# Set_Timer.net
KiCad netlist of a schematic drawn in Altium Designer
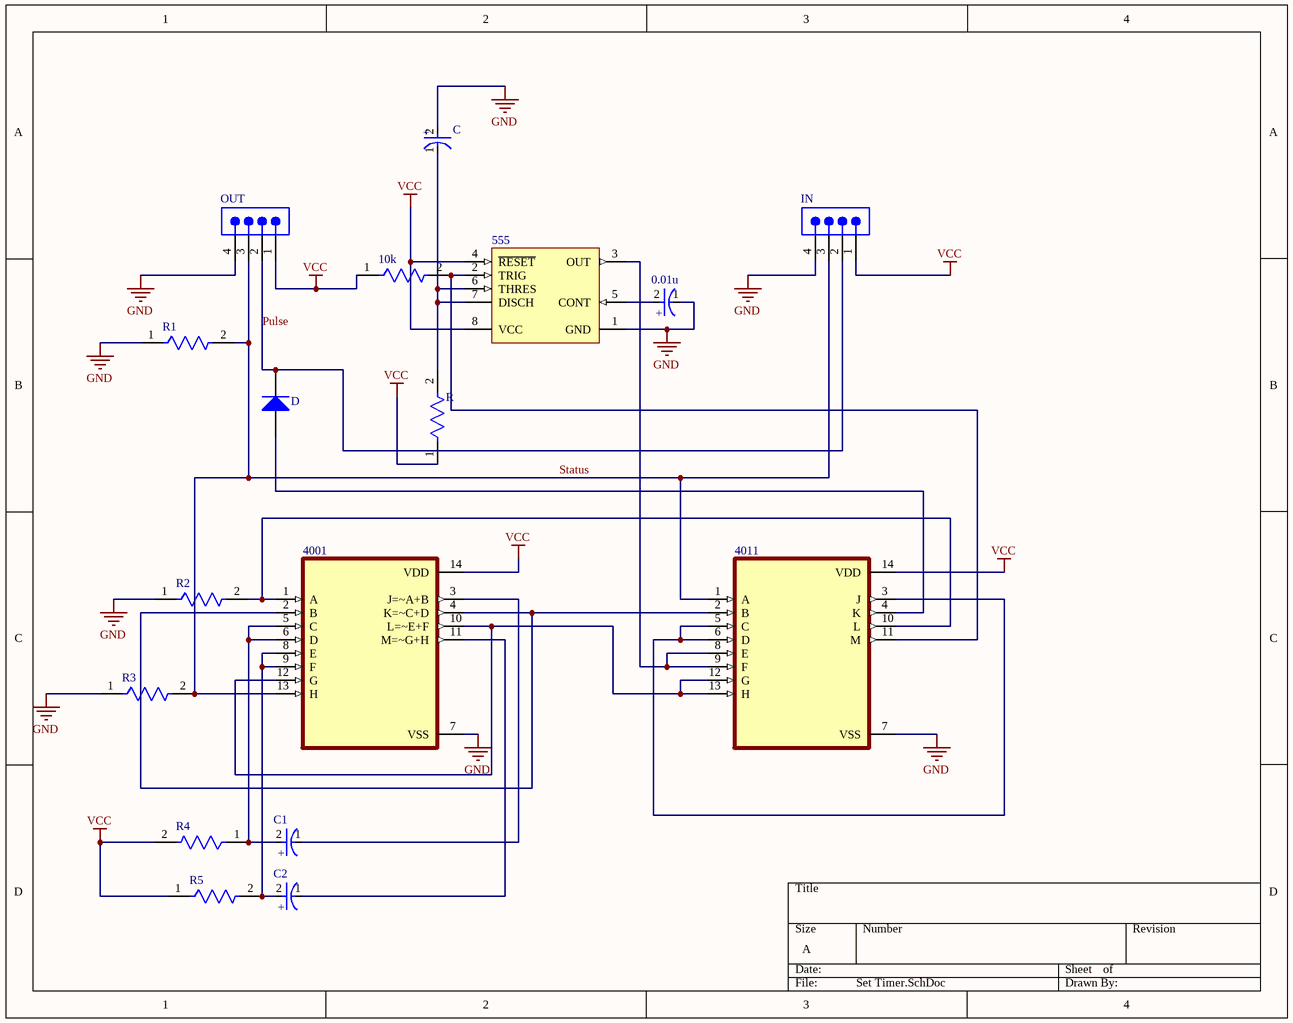
[diagram p0: Set Timer.SchDoc]

(export (version "E")
  (design (tool "Eeschema 10.0.6"))
  (components
    (comp (ref "0.01u")
      (value "EEUHD1H330")
      (footprint "FP-RAD-TH-D_5_0_5-L_11_1-MFG")
      (description "Aluminum Electrolytic Capacitors (Radial Lead Type) AEC-Q200 Qualified 33uF ±20% 50V")
      (fields (field (name "TOLERANCE") "20%") (field (name "VOLTAGE") "50V"))
      (libsource (lib "Altium Content Vault") (part "a00bbbee19879c290e62620ae7e47b1"))
    )
    (comp (ref "10k")
      (value "RR01J100KTB")
      (footprint "FP-RR01-MFG")
      (description "RES 100K OHM 5% 1W AXIAL")
      (fields (field (name "TOLERANCE") "5%"))
      (libsource (lib "Altium Content Vault") (part "1029c3af85768c4190bb7ad29bc67b5"))
    )
    (comp (ref "555")
      (value "NE555P")
      (footprint "P0008A")
      (description "Precision Timer, 4.5 to 16 V, 0 to 70 degC, 8-Pin DIP, Pb-Free, Tube")
      (fields (field (name "MANUFACTURER") "TexasInstruments"))
      (libsource (lib "Altium Content Vault") (part "TI-NE555-P8"))
    )
    (comp (ref "4001")
      (value "CD4001BE")
      (footprint "DIP794W45P254L1969H508Q14")
      (description "CMOS Quad 2-Input NOR Gate 14-PDIP -55 to 125")
      (fields (field (name "MF") "Texas Instruments"))
      (libsource (lib "CD4001BE") (part "CD4001BE"))
    )
    (comp (ref "4011")
      (value "CD4011BE")
      (footprint "DIP794W45P254L1969H508Q14")
      (libsource (lib "CD4011BE") (part "CD4011BE"))
    )
    (comp (ref "C")
      (value "EEUHD1H330")
      (footprint "FP-RAD-TH-D_5_0_5-L_11_1-MFG")
      (description "Aluminum Electrolytic Capacitors (Radial Lead Type) AEC-Q200 Qualified 33uF ±20% 50V")
      (fields (field (name "TOLERANCE") "20%") (field (name "VOLTAGE") "50V"))
      (libsource (lib "Altium Content Vault") (part "a00bbbee19879c290e62620ae7e47b1"))
    )
    (comp (ref "C1")
      (value "EEUHD1H330")
      (footprint "FP-RAD-TH-D_5_0_5-L_11_1-MFG")
      (description "Aluminum Electrolytic Capacitors (Radial Lead Type) AEC-Q200 Qualified 33uF ±20% 50V")
      (fields (field (name "TOLERANCE") "20%") (field (name "VOLTAGE") "50V"))
      (libsource (lib "Altium Content Vault") (part "a00bbbee19879c290e62620ae7e47b1"))
    )
    (comp (ref "C2")
      (value "EEUHD1H330")
      (footprint "FP-RAD-TH-D_5_0_5-L_11_1-MFG")
      (description "Aluminum Electrolytic Capacitors (Radial Lead Type) AEC-Q200 Qualified 33uF ±20% 50V")
      (fields (field (name "TOLERANCE") "20%") (field (name "VOLTAGE") "50V"))
      (libsource (lib "Altium Content Vault") (part "a00bbbee19879c290e62620ae7e47b1"))
    )
    (comp (ref "D")
      (value "1N4001-T")
      (footprint "DIOD-DO-41-P-2_V")
      (description "1.0 A Rectifier, 15 pF, 50 V, -65 to 150 degC, 2-Pin DO-41 Plastic, RoHS, Tape and Reel")
      (fields (field (name "MANUFACTURER") "Diodes Inc"))
      (libsource (lib "Altium Content Vault") (part "DIOD-D-A1K2-2"))
    )
    (comp (ref "IN")
      (value "TSW-104-08-L-S")
      (footprint "SMTC-TSW-104-08-X-S")
      (description "0.025\" SQ Post Header, Through-hole, Vertical, -55 to 125 degC, 2.54 mm Pitch, 4-Pin, Male, RoHS")
      (fields (field (name "MANUFACTURER") "Samtec"))
      (libsource (lib "Altium Content Vault") (part "SMTC-TSW-104-08-X-S"))
    )
    (comp (ref "OUT")
      (value "TSW-104-08-L-S")
      (footprint "SMTC-TSW-104-08-X-S")
      (description "0.025\" SQ Post Header, Through-hole, Vertical, -55 to 125 degC, 2.54 mm Pitch, 4-Pin, Male, RoHS")
      (fields (field (name "MANUFACTURER") "Samtec"))
      (libsource (lib "Altium Content Vault") (part "SMTC-TSW-104-08-X-S"))
    )
    (comp (ref "R")
      (value "RR01J100KTB")
      (footprint "FP-RR01-MFG")
      (description "RES 100K OHM 5% 1W AXIAL")
      (fields (field (name "TOLERANCE") "5%"))
      (libsource (lib "Altium Content Vault") (part "1029c3af85768c4190bb7ad29bc67b5"))
    )
    (comp (ref "R1")
      (value "RR01J100KTB")
      (footprint "FP-RR01-MFG")
      (description "RES 100K OHM 5% 1W AXIAL")
      (fields (field (name "TOLERANCE") "5%"))
      (libsource (lib "Altium Content Vault") (part "1029c3af85768c4190bb7ad29bc67b5"))
    )
    (comp (ref "R2")
      (value "RR01J100KTB")
      (footprint "FP-RR01-MFG")
      (description "RES 100K OHM 5% 1W AXIAL")
      (fields (field (name "TOLERANCE") "5%"))
      (libsource (lib "Altium Content Vault") (part "1029c3af85768c4190bb7ad29bc67b5"))
    )
    (comp (ref "R3")
      (value "RR01J100KTB")
      (footprint "FP-RR01-MFG")
      (description "RES 100K OHM 5% 1W AXIAL")
      (fields (field (name "TOLERANCE") "5%"))
      (libsource (lib "Altium Content Vault") (part "1029c3af85768c4190bb7ad29bc67b5"))
    )
    (comp (ref "R4")
      (value "RR01J100KTB")
      (footprint "FP-RR01-MFG")
      (description "RES 100K OHM 5% 1W AXIAL")
      (fields (field (name "TOLERANCE") "5%"))
      (libsource (lib "Altium Content Vault") (part "1029c3af85768c4190bb7ad29bc67b5"))
    )
    (comp (ref "R5")
      (value "RR01J100KTB")
      (footprint "FP-RR01-MFG")
      (description "RES 100K OHM 5% 1W AXIAL")
      (fields (field (name "TOLERANCE") "5%"))
      (libsource (lib "Altium Content Vault") (part "1029c3af85768c4190bb7ad29bc67b5"))
    )
  )
  (nets
    (net (code "1") (name "/Pulse") (class "Default")
      (node (ref "D") (pin "2") (pinfunction "K_2") (pintype "passive"))
      (node (ref "IN") (pin "2") (pinfunction "2_2") (pintype "passive"))
      (node (ref "OUT") (pin "2") (pinfunction "2_2") (pintype "passive"))
    )
    (net (code "2") (name "/Status") (class "Default")
      (node (ref "4001") (pin "13") (pinfunction "H_13") (pintype "input"))
      (node (ref "4011") (pin "1") (pinfunction "A_1") (pintype "input"))
      (node (ref "IN") (pin "3") (pinfunction "3_3") (pintype "passive"))
      (node (ref "OUT") (pin "3") (pinfunction "3_3") (pintype "passive"))
      (node (ref "R1") (pin "2") (pinfunction "2_2") (pintype "passive"))
      (node (ref "R3") (pin "2") (pinfunction "2_2") (pintype "passive"))
    )
    (net (code "3") (name "GND") (class "Default")
      (node (ref "0.01u") (pin "1") (pinfunction "C_1") (pintype "passive"))
      (node (ref "4001") (pin "7") (pinfunction "VSS_7") (pintype "power_in"))
      (node (ref "4011") (pin "7") (pinfunction "VSS_7") (pintype "power_in"))
      (node (ref "555") (pin "1") (pinfunction "GND_1") (pintype "power_in"))
      (node (ref "C") (pin "2") (pinfunction "A_2") (pintype "passive"))
      (node (ref "IN") (pin "4") (pinfunction "4_4") (pintype "passive"))
      (node (ref "OUT") (pin "4") (pinfunction "4_4") (pintype "passive"))
      (node (ref "R1") (pin "1") (pinfunction "1_1") (pintype "passive"))
      (node (ref "R2") (pin "1") (pinfunction "1_1") (pintype "passive"))
      (node (ref "R3") (pin "1") (pinfunction "1_1") (pintype "passive"))
    )
    (net (code "4") (name "Net-(0.01u-A)") (class "Default")
      (node (ref "0.01u") (pin "2") (pinfunction "A_2") (pintype "passive"))
      (node (ref "555") (pin "5") (pinfunction "CONT_5") (pintype "input"))
    )
    (net (code "5") (name "Net-(555-DISCH)") (class "Default")
      (node (ref "555") (pin "6") (pinfunction "THRES_6") (pintype "input"))
      (node (ref "555") (pin "7") (pinfunction "DISCH_7") (pintype "open_collector"))
      (node (ref "C") (pin "1") (pinfunction "C_1") (pintype "passive"))
      (node (ref "R") (pin "2") (pinfunction "2_2") (pintype "passive"))
    )
    (net (code "6") (name "Net-(4001-A)") (class "Default")
      (node (ref "4001") (pin "1") (pinfunction "A_1") (pintype "input"))
      (node (ref "4011") (pin "10") (pinfunction "L_10") (pintype "output"))
      (node (ref "R2") (pin "2") (pinfunction "2_2") (pintype "passive"))
    )
    (net (code "7") (name "Net-(4001-B)") (class "Default")
      (node (ref "4001") (pin "2") (pinfunction "B_2") (pintype "input"))
      (node (ref "4001") (pin "4") (pinfunction "K=~C+D_4") (pintype "output"))
      (node (ref "4011") (pin "2") (pinfunction "B_2") (pintype "input"))
    )
    (net (code "8") (name "Net-(4001-C)") (class "Default")
      (node (ref "4001") (pin "5") (pinfunction "C_5") (pintype "input"))
      (node (ref "4001") (pin "6") (pinfunction "D_6") (pintype "input"))
      (node (ref "C1") (pin "2") (pinfunction "A_2") (pintype "passive"))
      (node (ref "R4") (pin "1") (pinfunction "1_1") (pintype "passive"))
    )
    (net (code "9") (name "Net-(4001-E)") (class "Default")
      (node (ref "4001") (pin "8") (pinfunction "E_8") (pintype "input"))
      (node (ref "4001") (pin "9") (pinfunction "F_9") (pintype "input"))
      (node (ref "C2") (pin "2") (pinfunction "A_2") (pintype "passive"))
      (node (ref "R5") (pin "2") (pinfunction "2_2") (pintype "passive"))
    )
    (net (code "10") (name "Net-(4001-G)") (class "Default")
      (node (ref "4001") (pin "10") (pinfunction "L=~E+F_10") (pintype "output"))
      (node (ref "4001") (pin "12") (pinfunction "G_12") (pintype "input"))
      (node (ref "4011") (pin "12") (pinfunction "G_12") (pintype "input"))
      (node (ref "4011") (pin "13") (pinfunction "H_13") (pintype "input"))
    )
    (net (code "11") (name "Net-(4001-J=~A+B)") (class "Default")
      (node (ref "4001") (pin "3") (pinfunction "J=~A+B_3") (pintype "output"))
      (node (ref "C1") (pin "1") (pinfunction "C_1") (pintype "passive"))
    )
    (net (code "12") (name "Net-(4001-M=~G+H)") (class "Default")
      (node (ref "4001") (pin "11") (pinfunction "M=~G+H_11") (pintype "output"))
      (node (ref "C2") (pin "1") (pinfunction "C_1") (pintype "passive"))
    )
    (net (code "13") (name "Net-(4011-C)") (class "Default")
      (node (ref "4011") (pin "3") (pinfunction "J_3") (pintype "output"))
      (node (ref "4011") (pin "5") (pinfunction "C_5") (pintype "input"))
      (node (ref "4011") (pin "6") (pinfunction "D_6") (pintype "input"))
    )
    (net (code "14") (name "Net-(4011-E)") (class "Default")
      (node (ref "4011") (pin "8") (pinfunction "E_8") (pintype "input"))
      (node (ref "4011") (pin "9") (pinfunction "F_9") (pintype "input"))
      (node (ref "555") (pin "3") (pinfunction "OUT_3") (pintype "output"))
    )
    (net (code "15") (name "Net-(4011-K)") (class "Default")
      (node (ref "4011") (pin "4") (pinfunction "K_4") (pintype "output"))
      (node (ref "D") (pin "1") (pinfunction "A_1") (pintype "passive"))
    )
    (net (code "16") (name "Net-(4011-M)") (class "Default")
      (node (ref "10k") (pin "2") (pinfunction "2_2") (pintype "passive"))
      (node (ref "4011") (pin "11") (pinfunction "M_11") (pintype "output"))
      (node (ref "555") (pin "2") (pinfunction "TRIG_2") (pintype "input"))
    )
    (net (code "17") (name "VCC") (class "Default")
      (node (ref "10k") (pin "1") (pinfunction "1_1") (pintype "passive"))
      (node (ref "4001") (pin "14") (pinfunction "VDD_14") (pintype "power_in"))
      (node (ref "4011") (pin "14") (pinfunction "VDD_14") (pintype "power_in"))
      (node (ref "555") (pin "4") (pinfunction "~{RESET}_4") (pintype "input"))
      (node (ref "555") (pin "8") (pinfunction "VCC_8") (pintype "power_in"))
      (node (ref "IN") (pin "1") (pinfunction "1_1") (pintype "passive"))
      (node (ref "OUT") (pin "1") (pinfunction "1_1") (pintype "passive"))
      (node (ref "R") (pin "1") (pinfunction "1_1") (pintype "passive"))
      (node (ref "R4") (pin "2") (pinfunction "2_2") (pintype "passive"))
      (node (ref "R5") (pin "1") (pinfunction "1_1") (pintype "passive"))
    )
  )
)
